# 1-2.net
KiCad netlist of a schematic drawn in EAGLE
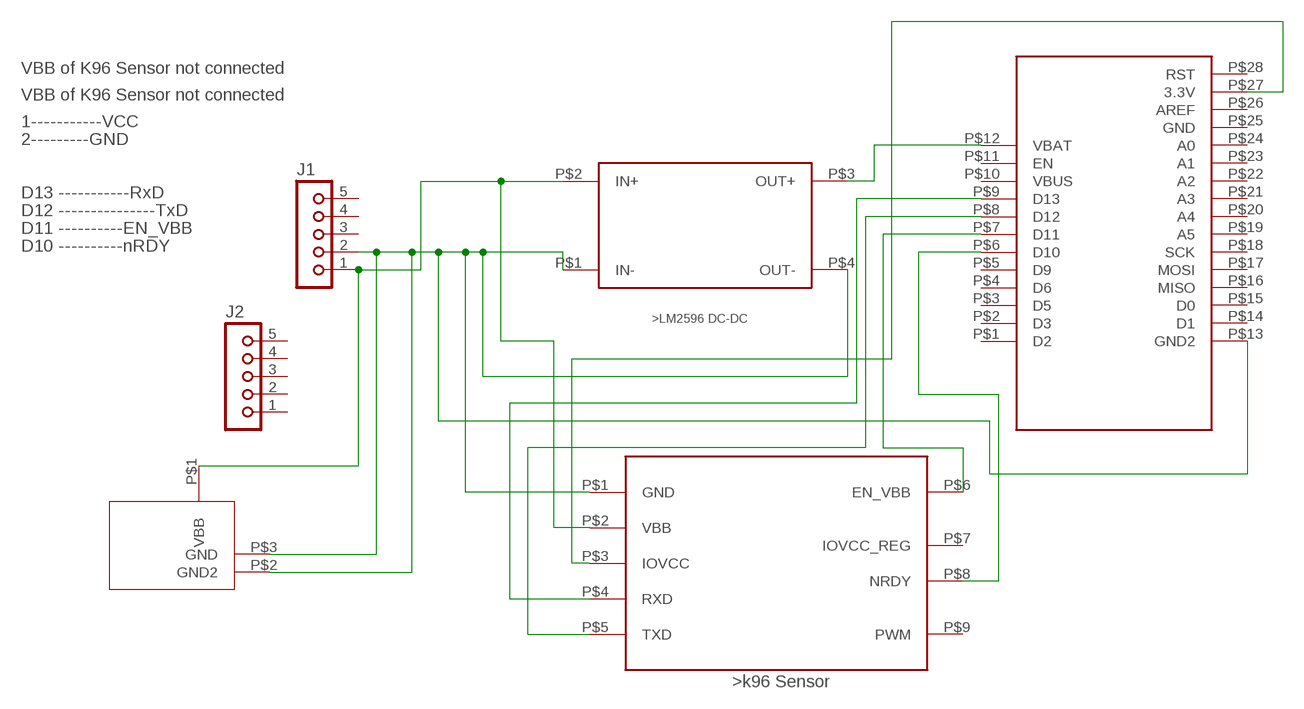
[diagram p0: schematic, sheet 1]

(export (version "E")
  (design (tool "Eeschema 10.0.6"))
  (components
    (comp (ref "DCDC1")
      (value "DCDC")
      (footprint "eagle-import:DCDC")
      (libsource (lib "eagle-import") (part "DCDC"))
    )
    (comp (ref "FEATHER1")
      (value "FEATHER")
      (footprint "eagle-import:FEATHER")
      (libsource (lib "eagle-import") (part "FEATHER"))
    )
    (comp (ref "J1")
      (value "JU05")
      (footprint "eagle-import:JU05")
      (libsource (lib "eagle-import") (part "JU05"))
    )
    (comp (ref "J2")
      (value "JU05")
      (footprint "eagle-import:JU05")
      (libsource (lib "eagle-import") (part "JU05"))
    )
    (comp (ref "K96SENSOR1")
      (value "K96SENSOR")
      (footprint "eagle-import:K96SENSOR")
      (libsource (lib "eagle-import") (part "K96SENSOR"))
    )
    (comp (ref "U$1")
      (value "POWER")
      (footprint "eagle-import:POWERIN")
      (libsource (lib "eagle-import") (part "POWER"))
    )
  )
  (nets
    (net (code "1") (name "Net-(DCDC1-IN+)") (class "Default")
      (node (ref "DCDC1") (pin "P$2") (pinfunction "IN+_P$2") (pintype "bidirectional"))
      (node (ref "J1") (pin "1") (pinfunction "1_1") (pintype "passive"))
      (node (ref "K96SENSOR1") (pin "P$2") (pinfunction "VBB_P$2") (pintype "bidirectional"))
      (node (ref "U$1") (pin "P$1") (pinfunction "VBB_P$1") (pintype "bidirectional"))
    )
    (net (code "2") (name "Net-(DCDC1-IN-)") (class "Default")
      (node (ref "DCDC1") (pin "P$1") (pinfunction "IN-_P$1") (pintype "bidirectional"))
      (node (ref "DCDC1") (pin "P$4") (pinfunction "OUT-_P$4") (pintype "bidirectional"))
      (node (ref "FEATHER1") (pin "P$13") (pinfunction "GND2_P$13") (pintype "bidirectional"))
      (node (ref "J1") (pin "2") (pinfunction "2_2") (pintype "passive"))
      (node (ref "K96SENSOR1") (pin "P$1") (pinfunction "GND_P$1") (pintype "bidirectional"))
      (node (ref "U$1") (pin "P$2") (pinfunction "GND2_P$2") (pintype "bidirectional"))
      (node (ref "U$1") (pin "P$3") (pinfunction "GND_P$3") (pintype "bidirectional"))
    )
    (net (code "3") (name "Net-(DCDC1-OUT+)") (class "Default")
      (node (ref "DCDC1") (pin "P$3") (pinfunction "OUT+_P$3") (pintype "bidirectional"))
      (node (ref "FEATHER1") (pin "P$12") (pinfunction "VBAT_P$12") (pintype "bidirectional"))
    )
    (net (code "4") (name "Net-(FEATHER1-3.3V)") (class "Default")
      (node (ref "FEATHER1") (pin "P$27") (pinfunction "3.3V_P$27") (pintype "bidirectional"))
      (node (ref "K96SENSOR1") (pin "P$3") (pinfunction "IOVCC_P$3") (pintype "bidirectional"))
    )
    (net (code "5") (name "Net-(FEATHER1-D10)") (class "Default")
      (node (ref "FEATHER1") (pin "P$6") (pinfunction "D10_P$6") (pintype "bidirectional"))
      (node (ref "K96SENSOR1") (pin "P$8") (pinfunction "NRDY_P$8") (pintype "bidirectional"))
    )
    (net (code "6") (name "Net-(FEATHER1-D11)") (class "Default")
      (node (ref "FEATHER1") (pin "P$7") (pinfunction "D11_P$7") (pintype "bidirectional"))
      (node (ref "K96SENSOR1") (pin "P$6") (pinfunction "EN_VBB_P$6") (pintype "bidirectional"))
    )
    (net (code "7") (name "Net-(FEATHER1-D12)") (class "Default")
      (node (ref "FEATHER1") (pin "P$8") (pinfunction "D12_P$8") (pintype "bidirectional"))
      (node (ref "K96SENSOR1") (pin "P$5") (pinfunction "TXD_P$5") (pintype "bidirectional"))
    )
    (net (code "8") (name "Net-(FEATHER1-D13)") (class "Default")
      (node (ref "FEATHER1") (pin "P$9") (pinfunction "D13_P$9") (pintype "bidirectional"))
      (node (ref "K96SENSOR1") (pin "P$4") (pinfunction "RXD_P$4") (pintype "bidirectional"))
    )
    (net (code "9") (name "unconnected-(FEATHER1-A0-PadP$24)") (class "Default")
      (node (ref "FEATHER1") (pin "P$24") (pinfunction "A0_P$24") (pintype "bidirectional"))
    )
    (net (code "10") (name "unconnected-(FEATHER1-A1-PadP$23)") (class "Default")
      (node (ref "FEATHER1") (pin "P$23") (pinfunction "A1_P$23") (pintype "bidirectional"))
    )
    (net (code "11") (name "unconnected-(FEATHER1-A2-PadP$22)") (class "Default")
      (node (ref "FEATHER1") (pin "P$22") (pinfunction "A2_P$22") (pintype "bidirectional"))
    )
    (net (code "12") (name "unconnected-(FEATHER1-A3-PadP$21)") (class "Default")
      (node (ref "FEATHER1") (pin "P$21") (pinfunction "A3_P$21") (pintype "bidirectional"))
    )
    (net (code "13") (name "unconnected-(FEATHER1-A4-PadP$20)") (class "Default")
      (node (ref "FEATHER1") (pin "P$20") (pinfunction "A4_P$20") (pintype "bidirectional"))
    )
    (net (code "14") (name "unconnected-(FEATHER1-A5-PadP$19)") (class "Default")
      (node (ref "FEATHER1") (pin "P$19") (pinfunction "A5_P$19") (pintype "bidirectional"))
    )
    (net (code "15") (name "unconnected-(FEATHER1-AREF-PadP$26)") (class "Default")
      (node (ref "FEATHER1") (pin "P$26") (pinfunction "AREF_P$26") (pintype "bidirectional"))
    )
    (net (code "16") (name "unconnected-(FEATHER1-D0-PadP$15)") (class "Default")
      (node (ref "FEATHER1") (pin "P$15") (pinfunction "D0_P$15") (pintype "bidirectional"))
    )
    (net (code "17") (name "unconnected-(FEATHER1-D1-PadP$14)") (class "Default")
      (node (ref "FEATHER1") (pin "P$14") (pinfunction "D1_P$14") (pintype "bidirectional"))
    )
    (net (code "18") (name "unconnected-(FEATHER1-D2-PadP$1)") (class "Default")
      (node (ref "FEATHER1") (pin "P$1") (pinfunction "D2_P$1") (pintype "bidirectional"))
    )
    (net (code "19") (name "unconnected-(FEATHER1-D3-PadP$2)") (class "Default")
      (node (ref "FEATHER1") (pin "P$2") (pinfunction "D3_P$2") (pintype "bidirectional"))
    )
    (net (code "20") (name "unconnected-(FEATHER1-D5-PadP$3)") (class "Default")
      (node (ref "FEATHER1") (pin "P$3") (pinfunction "D5_P$3") (pintype "bidirectional"))
    )
    (net (code "21") (name "unconnected-(FEATHER1-D6-PadP$4)") (class "Default")
      (node (ref "FEATHER1") (pin "P$4") (pinfunction "D6_P$4") (pintype "bidirectional"))
    )
    (net (code "22") (name "unconnected-(FEATHER1-D9-PadP$5)") (class "Default")
      (node (ref "FEATHER1") (pin "P$5") (pinfunction "D9_P$5") (pintype "bidirectional"))
    )
    (net (code "23") (name "unconnected-(FEATHER1-EN-PadP$11)") (class "Default")
      (node (ref "FEATHER1") (pin "P$11") (pinfunction "EN_P$11") (pintype "bidirectional"))
    )
    (net (code "24") (name "unconnected-(FEATHER1-GND-PadP$25)") (class "Default")
      (node (ref "FEATHER1") (pin "P$25") (pinfunction "GND_P$25") (pintype "bidirectional"))
    )
    (net (code "25") (name "unconnected-(FEATHER1-MISO-PadP$16)") (class "Default")
      (node (ref "FEATHER1") (pin "P$16") (pinfunction "MISO_P$16") (pintype "bidirectional"))
    )
    (net (code "26") (name "unconnected-(FEATHER1-MOSI-PadP$17)") (class "Default")
      (node (ref "FEATHER1") (pin "P$17") (pinfunction "MOSI_P$17") (pintype "bidirectional"))
    )
    (net (code "27") (name "unconnected-(FEATHER1-RST-PadP$28)") (class "Default")
      (node (ref "FEATHER1") (pin "P$28") (pinfunction "RST_P$28") (pintype "bidirectional"))
    )
    (net (code "28") (name "unconnected-(FEATHER1-SCK-PadP$18)") (class "Default")
      (node (ref "FEATHER1") (pin "P$18") (pinfunction "SCK_P$18") (pintype "bidirectional"))
    )
    (net (code "29") (name "unconnected-(FEATHER1-VBUS-PadP$10)") (class "Default")
      (node (ref "FEATHER1") (pin "P$10") (pinfunction "VBUS_P$10") (pintype "bidirectional"))
    )
    (net (code "30") (name "unconnected-(J1-Pad3)") (class "Default")
      (node (ref "J1") (pin "3") (pinfunction "3_3") (pintype "passive"))
    )
    (net (code "31") (name "unconnected-(J1-Pad4)") (class "Default")
      (node (ref "J1") (pin "4") (pinfunction "4_4") (pintype "passive"))
    )
    (net (code "32") (name "unconnected-(J1-Pad5)") (class "Default")
      (node (ref "J1") (pin "5") (pinfunction "5_5") (pintype "passive"))
    )
    (net (code "33") (name "unconnected-(J2-Pad1)") (class "Default")
      (node (ref "J2") (pin "1") (pinfunction "1_1") (pintype "passive"))
    )
    (net (code "34") (name "unconnected-(J2-Pad2)") (class "Default")
      (node (ref "J2") (pin "2") (pinfunction "2_2") (pintype "passive"))
    )
    (net (code "35") (name "unconnected-(J2-Pad3)") (class "Default")
      (node (ref "J2") (pin "3") (pinfunction "3_3") (pintype "passive"))
    )
    (net (code "36") (name "unconnected-(J2-Pad4)") (class "Default")
      (node (ref "J2") (pin "4") (pinfunction "4_4") (pintype "passive"))
    )
    (net (code "37") (name "unconnected-(J2-Pad5)") (class "Default")
      (node (ref "J2") (pin "5") (pinfunction "5_5") (pintype "passive"))
    )
    (net (code "38") (name "unconnected-(K96SENSOR1-IOVCC_REG-PadP$7)") (class "Default")
      (node (ref "K96SENSOR1") (pin "P$7") (pinfunction "IOVCC_REG_P$7") (pintype "bidirectional"))
    )
    (net (code "39") (name "unconnected-(K96SENSOR1-PWM-PadP$9)") (class "Default")
      (node (ref "K96SENSOR1") (pin "P$9") (pinfunction "PWM_P$9") (pintype "bidirectional"))
    )
  )
)
